# lm2765gizmo.net
KiCad netlist of a schematic drawn in EAGLE
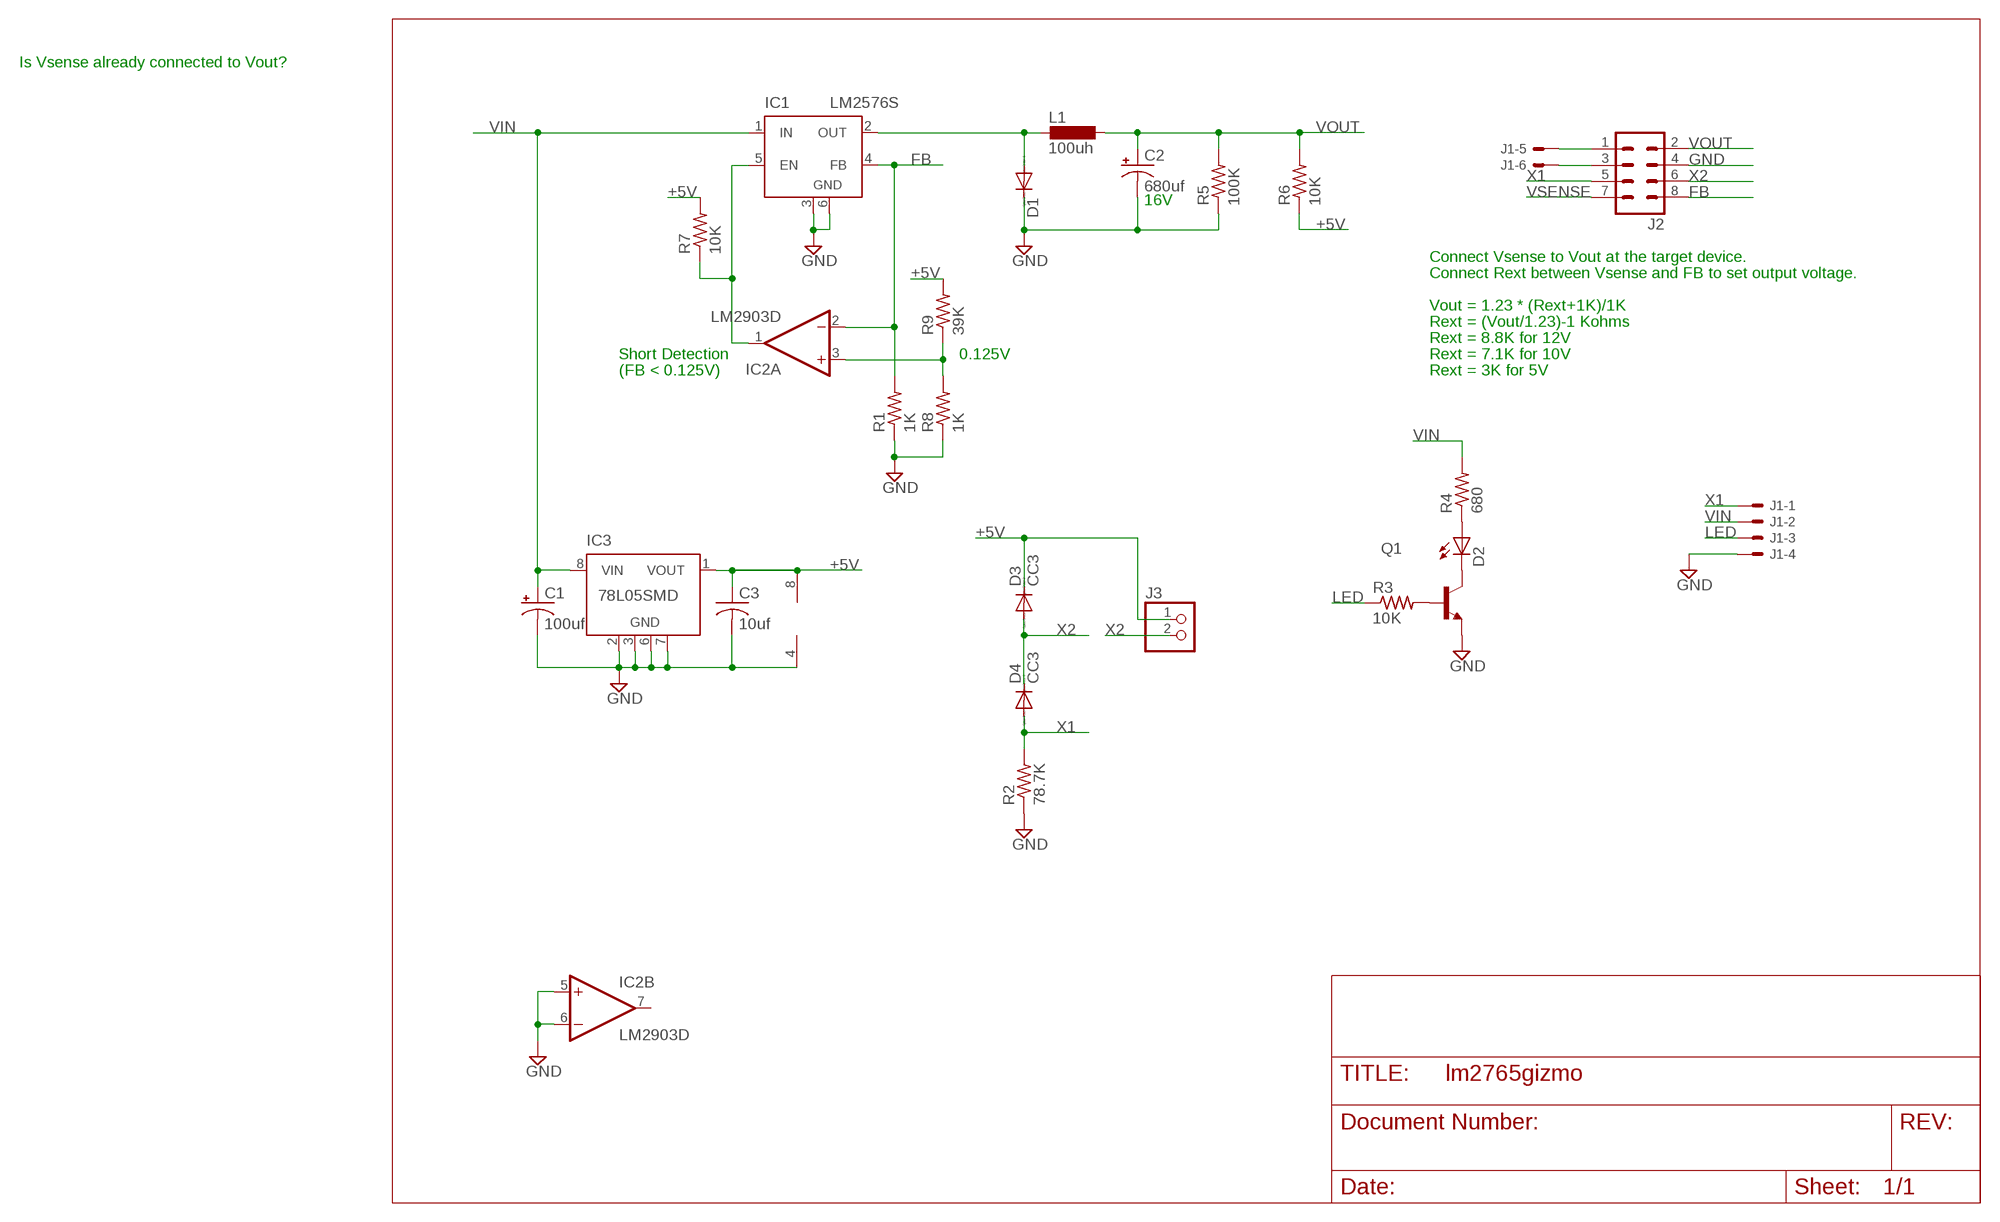
[diagram p0: schematic, sheet 1]

(export (version "E")
  (design (tool "Eeschema 10.0.6"))
  (components
    (comp (ref "C1")
      (value "100uf")
      (footprint "eagle-import:140CLH-0810")
      (libsource (lib "eagle-import") (part "CPOL-US140CLH-0810"))
    )
    (comp (ref "C2")
      (value "680uf")
      (footprint "eagle-import:140CLH-1014")
      (libsource (lib "eagle-import") (part "CPOL-US140CLH-1014"))
    )
    (comp (ref "C3")
      (value "10uf")
      (footprint "eagle-import:C0805")
      (libsource (lib "eagle-import") (part "C-USC0805"))
    )
    (comp (ref "D1")
      (value "DIODE-SMC")
      (footprint "eagle-import:SMC")
      (libsource (lib "eagle-import") (part "DIODE-SMC"))
    )
    (comp (ref "D2")
      (value "LEDCHIP-LED0805")
      (footprint "eagle-import:CHIP-LED0805")
      (libsource (lib "eagle-import") (part "LEDCHIP-LED0805"))
    )
    (comp (ref "D3")
      (value "CC3")
      (footprint "eagle-import:SOD80C")
      (libsource (lib "eagle-import") (part "PMLL4150"))
    )
    (comp (ref "D4")
      (value "CC3")
      (footprint "eagle-import:SOD80C")
      (libsource (lib "eagle-import") (part "PMLL4150"))
    )
    (comp (ref "IC1")
      (value "LM2576S")
      (footprint "eagle-import:TO263-5")
      (libsource (lib "eagle-import") (part "LM2596S"))
    )
    (comp (ref "IC2")
      (value "LM2903D")
      (footprint "eagle-import:SO08")
      (libsource (lib "eagle-import") (part "LM2903D"))
    )
    (comp (ref "IC3")
      (value "78L05SMD")
      (footprint "eagle-import:SO08")
      (libsource (lib "eagle-import") (part "78LSMD05"))
    )
    (comp (ref "J1")
      (value "53261-06")
      (footprint "eagle-import:53261-06")
      (libsource (lib "eagle-import") (part "53?-06261"))
    )
    (comp (ref "J2")
      (value "MA04-2")
      (footprint "eagle-import:MA04-2")
      (libsource (lib "eagle-import") (part "MA04-2"))
    )
    (comp (ref "J3")
      (value "PINHD-1X2")
      (footprint "eagle-import:1X02")
      (libsource (lib "eagle-import") (part "PINHD-1X2"))
    )
    (comp (ref "L1")
      (value "100uh")
      (footprint "eagle-import:DO3316P")
      (libsource (lib "eagle-import") (part "DO3316P"))
    )
    (comp (ref "Q1")
      (value "BC808-NPN-SOT23-BEC")
      (footprint "eagle-import:SOT23-BEC")
      (libsource (lib "eagle-import") (part "-NPN-SOT23-BECBC808"))
    )
    (comp (ref "R1")
      (value "1K")
      (footprint "eagle-import:M0805")
      (libsource (lib "eagle-import") (part "R-US_M0805"))
    )
    (comp (ref "R2")
      (value "78.7K")
      (footprint "eagle-import:M0805")
      (libsource (lib "eagle-import") (part "R-US_M0805"))
    )
    (comp (ref "R3")
      (value "10K")
      (footprint "eagle-import:M0805")
      (libsource (lib "eagle-import") (part "R-US_M0805"))
    )
    (comp (ref "R4")
      (value "680")
      (footprint "eagle-import:M0805")
      (libsource (lib "eagle-import") (part "R-US_M0805"))
    )
    (comp (ref "R5")
      (value "100K")
      (footprint "eagle-import:M0805")
      (libsource (lib "eagle-import") (part "R-US_M0805"))
    )
    (comp (ref "R6")
      (value "10K")
      (footprint "eagle-import:M0805")
      (libsource (lib "eagle-import") (part "R-US_M0805"))
    )
    (comp (ref "R7")
      (value "10K")
      (footprint "eagle-import:M0805")
      (libsource (lib "eagle-import") (part "R-US_M0805"))
    )
    (comp (ref "R8")
      (value "1K")
      (footprint "eagle-import:M0805")
      (libsource (lib "eagle-import") (part "R-US_M0805"))
    )
    (comp (ref "R9")
      (value "39K")
      (footprint "eagle-import:M0805")
      (libsource (lib "eagle-import") (part "R-US_M0805"))
    )
  )
  (nets
    (net (code "1") (name "/+5V") (class "Default")
      (node (ref "C3") (pin "1") (pinfunction "1_1") (pintype "passive"))
      (node (ref "D3") (pin "C") (pinfunction "C_C") (pintype "passive"))
      (node (ref "IC2") (pin "8") (pinfunction "V+_8") (pintype "power_in"))
      (node (ref "IC3") (pin "1") (pinfunction "VOUT_1") (pintype "output"))
      (node (ref "J3") (pin "1") (pinfunction "1_1") (pintype "passive"))
      (node (ref "R6") (pin "1") (pinfunction "1_1") (pintype "passive"))
      (node (ref "R7") (pin "2") (pinfunction "2_2") (pintype "passive"))
      (node (ref "R9") (pin "2") (pinfunction "2_2") (pintype "passive"))
    )
    (net (code "2") (name "/FB") (class "Default")
      (node (ref "IC1") (pin "4") (pinfunction "FB_4") (pintype "input"))
      (node (ref "IC2") (pin "2") (pinfunction "-IN_2") (pintype "input"))
      (node (ref "J2") (pin "8") (pinfunction "8_8") (pintype "passive"))
      (node (ref "R1") (pin "2") (pinfunction "2_2") (pintype "passive"))
    )
    (net (code "3") (name "/LED") (class "Default")
      (node (ref "J1") (pin "3") (pinfunction "S_3") (pintype "passive"))
      (node (ref "R3") (pin "1") (pinfunction "1_1") (pintype "passive"))
    )
    (net (code "4") (name "/VIN") (class "Default")
      (node (ref "C1") (pin "+") (pinfunction "+_+") (pintype "passive"))
      (node (ref "IC1") (pin "1") (pinfunction "IN_1") (pintype "input"))
      (node (ref "IC3") (pin "8") (pinfunction "VIN_8") (pintype "passive"))
      (node (ref "J1") (pin "2") (pinfunction "S_2") (pintype "passive"))
      (node (ref "R4") (pin "2") (pinfunction "2_2") (pintype "passive"))
    )
    (net (code "5") (name "/VOUT") (class "Default")
      (node (ref "C2") (pin "+") (pinfunction "+_+") (pintype "passive"))
      (node (ref "J2") (pin "2") (pinfunction "2_2") (pintype "passive"))
      (node (ref "L1") (pin "2") (pinfunction "2_2") (pintype "passive"))
      (node (ref "R5") (pin "2") (pinfunction "2_2") (pintype "passive"))
      (node (ref "R6") (pin "2") (pinfunction "2_2") (pintype "passive"))
    )
    (net (code "6") (name "/VSENSE") (class "Default")
      (node (ref "J2") (pin "7") (pinfunction "7_7") (pintype "passive"))
    )
    (net (code "7") (name "/X1") (class "Default")
      (node (ref "D4") (pin "A") (pinfunction "A_A") (pintype "passive"))
      (node (ref "J1") (pin "1") (pinfunction "S_1") (pintype "passive"))
      (node (ref "J2") (pin "5") (pinfunction "5_5") (pintype "passive"))
      (node (ref "R2") (pin "2") (pinfunction "2_2") (pintype "passive"))
    )
    (net (code "8") (name "/X2") (class "Default")
      (node (ref "D3") (pin "A") (pinfunction "A_A") (pintype "passive"))
      (node (ref "D4") (pin "C") (pinfunction "C_C") (pintype "passive"))
      (node (ref "J2") (pin "6") (pinfunction "6_6") (pintype "passive"))
      (node (ref "J3") (pin "2") (pinfunction "2_2") (pintype "passive"))
    )
    (net (code "9") (name "GND") (class "Default")
      (node (ref "C1") (pin "-") (pinfunction "-_-") (pintype "passive"))
      (node (ref "C2") (pin "-") (pinfunction "-_-") (pintype "passive"))
      (node (ref "C3") (pin "2") (pinfunction "2_2") (pintype "passive"))
      (node (ref "D1") (pin "C") (pinfunction "C_C") (pintype "passive"))
      (node (ref "IC1") (pin "3") (pinfunction "GND_3") (pintype "power_in"))
      (node (ref "IC1") (pin "6") (pinfunction "GND_6") (pintype "power_in"))
      (node (ref "IC2") (pin "4") (pinfunction "V-_4") (pintype "power_in"))
      (node (ref "IC2") (pin "5") (pinfunction "+IN_5") (pintype "input"))
      (node (ref "IC2") (pin "6") (pinfunction "-IN_6") (pintype "input"))
      (node (ref "IC3") (pin "2") (pinfunction "GND_2") (pintype "power_in"))
      (node (ref "IC3") (pin "3") (pinfunction "GND_3") (pintype "power_in"))
      (node (ref "IC3") (pin "6") (pinfunction "GND_6") (pintype "power_in"))
      (node (ref "IC3") (pin "7") (pinfunction "GND_7") (pintype "power_in"))
      (node (ref "J1") (pin "4") (pinfunction "S_4") (pintype "passive"))
      (node (ref "J2") (pin "4") (pinfunction "4_4") (pintype "passive"))
      (node (ref "Q1") (pin "E") (pinfunction "E_E") (pintype "passive"))
      (node (ref "R1") (pin "1") (pinfunction "1_1") (pintype "passive"))
      (node (ref "R2") (pin "1") (pinfunction "1_1") (pintype "passive"))
      (node (ref "R5") (pin "1") (pinfunction "1_1") (pintype "passive"))
      (node (ref "R8") (pin "1") (pinfunction "1_1") (pintype "passive"))
    )
    (net (code "10") (name "Net-(D2-PadA)") (class "Default")
      (node (ref "D2") (pin "A") (pinfunction "A_A") (pintype "passive"))
      (node (ref "R4") (pin "1") (pinfunction "1_1") (pintype "passive"))
    )
    (net (code "11") (name "Net-(D2-PadC)") (class "Default")
      (node (ref "D2") (pin "C") (pinfunction "C_C") (pintype "passive"))
      (node (ref "Q1") (pin "C") (pinfunction "C_C") (pintype "passive"))
    )
    (net (code "12") (name "Net-(IC1-EN)") (class "Default")
      (node (ref "IC1") (pin "5") (pinfunction "EN_5") (pintype "input"))
      (node (ref "IC2") (pin "1") (pinfunction "OUT_1") (pintype "output"))
      (node (ref "R7") (pin "1") (pinfunction "1_1") (pintype "passive"))
    )
    (net (code "13") (name "Net-(IC1-OUT)") (class "Default")
      (node (ref "D1") (pin "A") (pinfunction "A_A") (pintype "passive"))
      (node (ref "IC1") (pin "2") (pinfunction "OUT_2") (pintype "output"))
      (node (ref "L1") (pin "1") (pinfunction "1_1") (pintype "passive"))
    )
    (net (code "14") (name "Net-(IC2A-+IN)") (class "Default")
      (node (ref "IC2") (pin "3") (pinfunction "+IN_3") (pintype "input"))
      (node (ref "R8") (pin "2") (pinfunction "2_2") (pintype "passive"))
      (node (ref "R9") (pin "1") (pinfunction "1_1") (pintype "passive"))
    )
    (net (code "15") (name "Net-(J1E-S)") (class "Default")
      (node (ref "J1") (pin "5") (pinfunction "S_5") (pintype "passive"))
      (node (ref "J2") (pin "1") (pinfunction "1_1") (pintype "passive"))
    )
    (net (code "16") (name "Net-(J1F-S)") (class "Default")
      (node (ref "J1") (pin "6") (pinfunction "S_6") (pintype "passive"))
      (node (ref "J2") (pin "3") (pinfunction "3_3") (pintype "passive"))
    )
    (net (code "17") (name "Net-(Q1-PadB)") (class "Default")
      (node (ref "Q1") (pin "B") (pinfunction "B_B") (pintype "passive"))
      (node (ref "R3") (pin "2") (pinfunction "2_2") (pintype "passive"))
    )
    (net (code "18") (name "unconnected-(IC2B-OUT-Pad7)") (class "Default")
      (node (ref "IC2") (pin "7") (pinfunction "OUT_7") (pintype "output"))
    )
  )
)
